# USB3HUB.net
KiCad netlist of a schematic drawn in Altium Designer
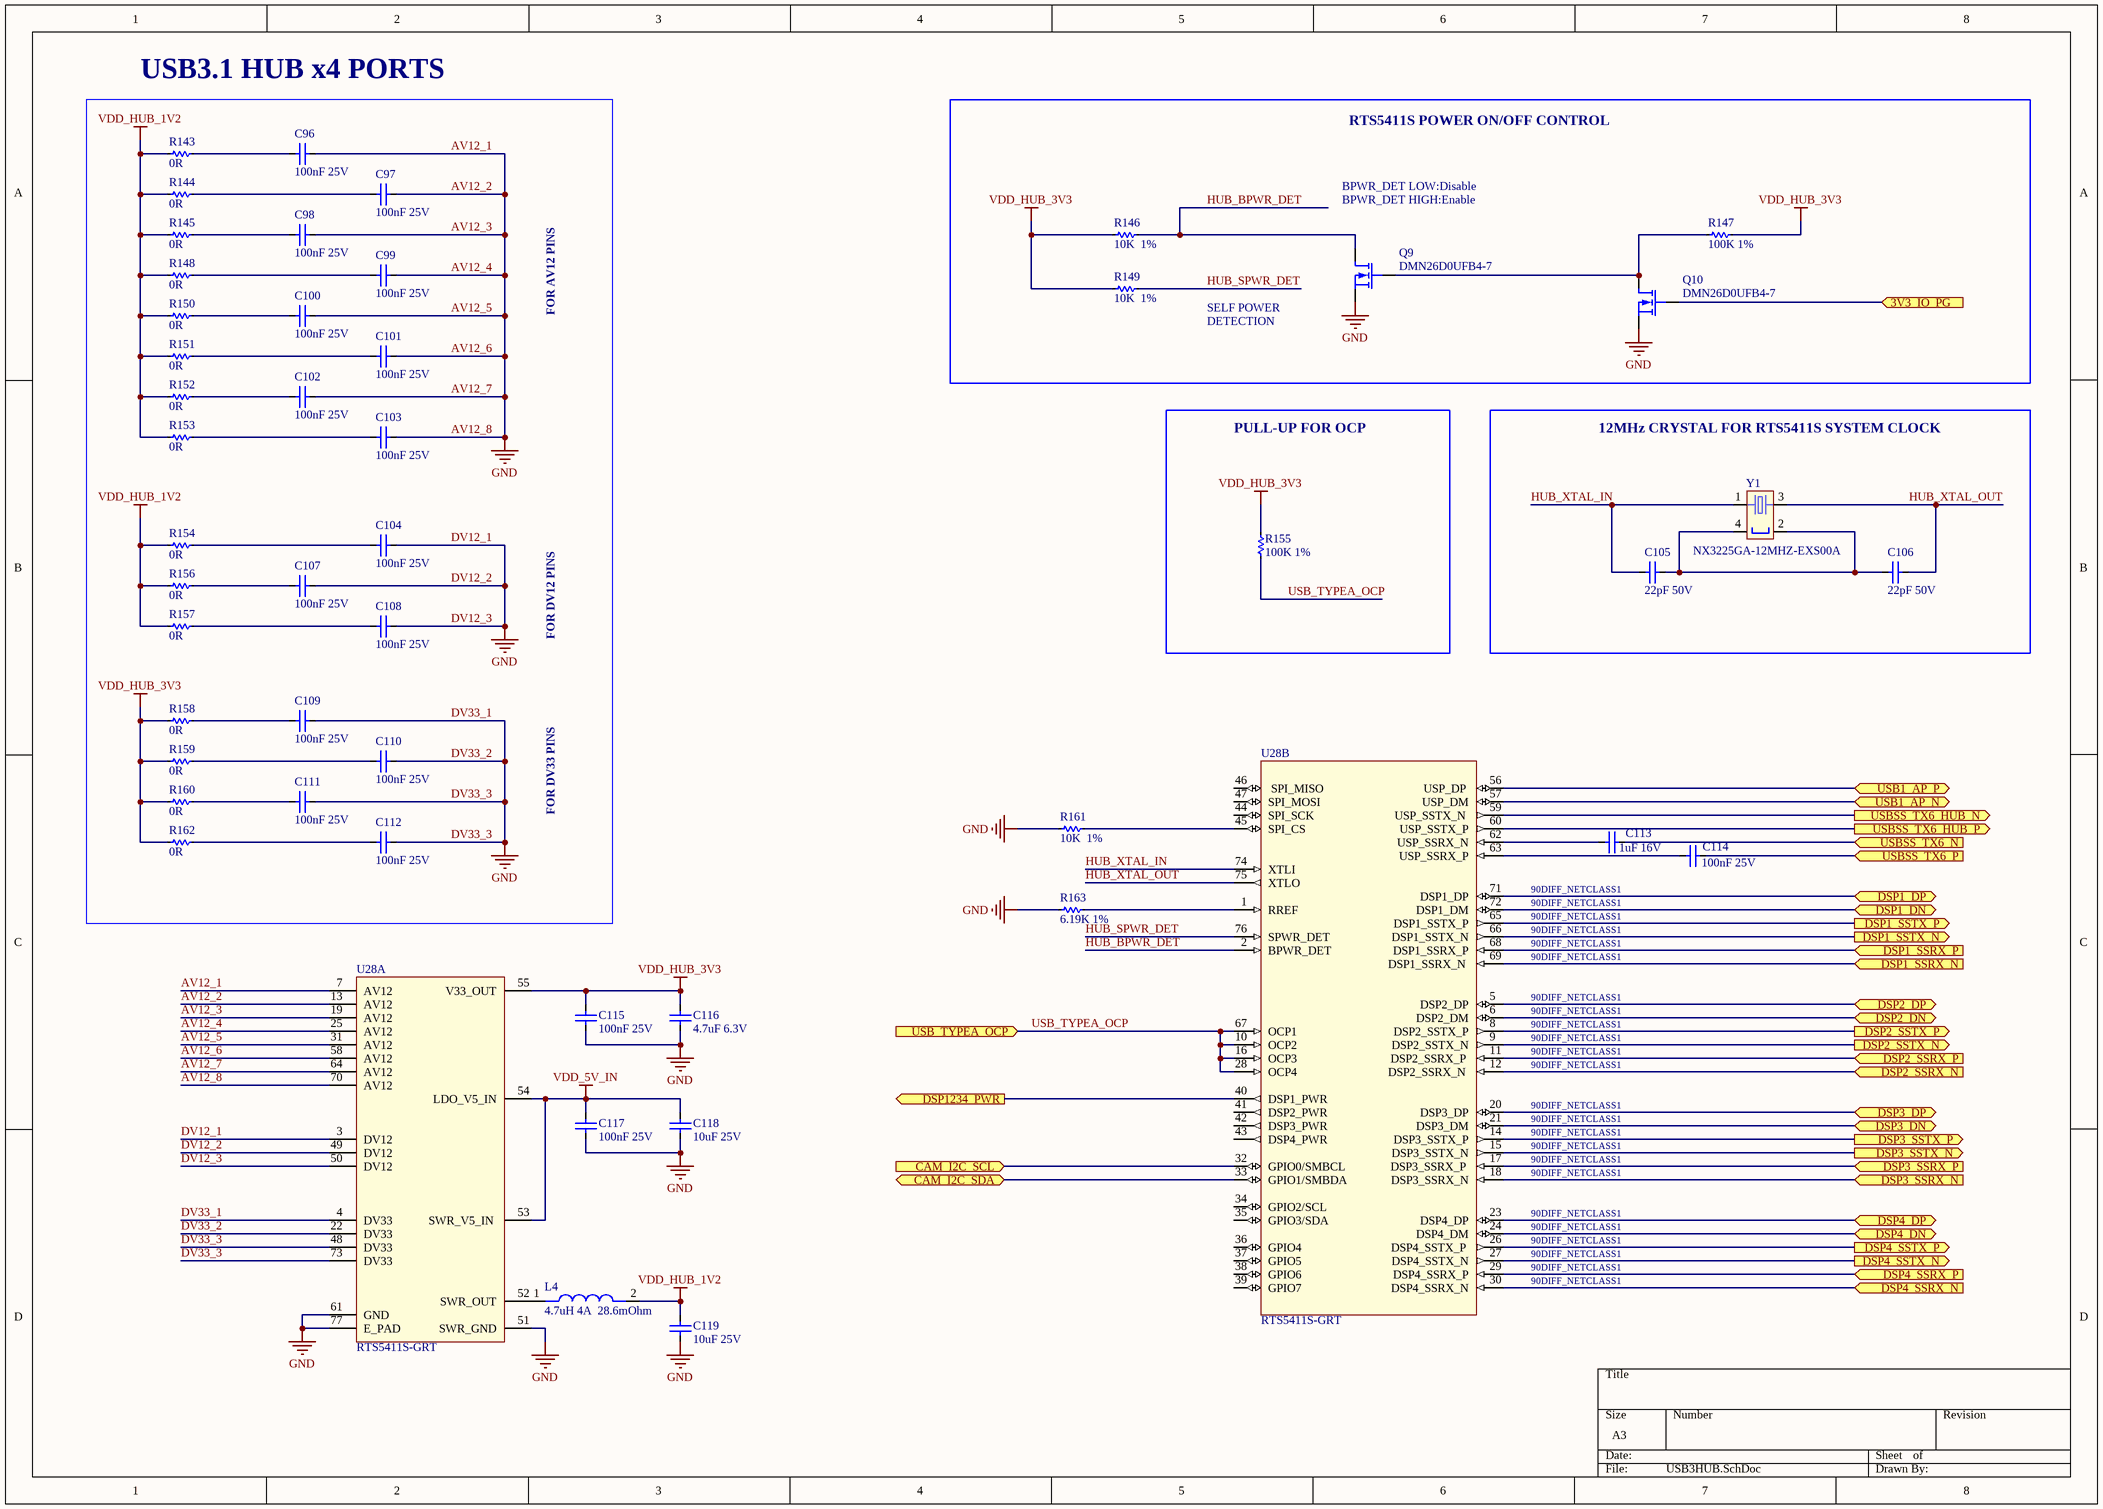
[diagram p0: USB3HUB.SchDoc]

(export (version "E")
  (design (tool "Eeschema 10.0.6"))
  (components
    (comp (ref "C96")
      (value "100nF 25V")
      (footprint "C0402")
      (description "CAP CER 0.1UF 25V X5R 0402 / High Value Multilayer Ceramic Capacitors (High dielectric type)")
      (fields
        (field (name "MANUFACTURER") "Taiyo Yuden")
        (field (name "MANUFACTURER PART NUMBER") "TMK105BJ104KV-F")
      )
      (libsource (lib "GM_Altium_Library") (part "TMK105BJ104KV-F"))
    )
    (comp (ref "C97")
      (value "100nF 25V")
      (footprint "C0402")
      (description "CAP CER 0.1UF 25V X5R 0402 / High Value Multilayer Ceramic Capacitors (High dielectric type)")
      (fields
        (field (name "MANUFACTURER") "Taiyo Yuden")
        (field (name "MANUFACTURER PART NUMBER") "TMK105BJ104KV-F")
      )
      (libsource (lib "GM_Altium_Library") (part "TMK105BJ104KV-F"))
    )
    (comp (ref "C98")
      (value "100nF 25V")
      (footprint "C0402")
      (description "CAP CER 0.1UF 25V X5R 0402 / High Value Multilayer Ceramic Capacitors (High dielectric type)")
      (fields
        (field (name "MANUFACTURER") "Taiyo Yuden")
        (field (name "MANUFACTURER PART NUMBER") "TMK105BJ104KV-F")
      )
      (libsource (lib "GM_Altium_Library") (part "TMK105BJ104KV-F"))
    )
    (comp (ref "C99")
      (value "100nF 25V")
      (footprint "C0402")
      (description "CAP CER 0.1UF 25V X5R 0402 / High Value Multilayer Ceramic Capacitors (High dielectric type)")
      (fields
        (field (name "MANUFACTURER") "Taiyo Yuden")
        (field (name "MANUFACTURER PART NUMBER") "TMK105BJ104KV-F")
      )
      (libsource (lib "GM_Altium_Library") (part "TMK105BJ104KV-F"))
    )
    (comp (ref "C100")
      (value "100nF 25V")
      (footprint "C0402")
      (description "CAP CER 0.1UF 25V X5R 0402 / High Value Multilayer Ceramic Capacitors (High dielectric type)")
      (fields
        (field (name "MANUFACTURER") "Taiyo Yuden")
        (field (name "MANUFACTURER PART NUMBER") "TMK105BJ104KV-F")
      )
      (libsource (lib "GM_Altium_Library") (part "TMK105BJ104KV-F"))
    )
    (comp (ref "C101")
      (value "100nF 25V")
      (footprint "C0402")
      (description "CAP CER 0.1UF 25V X5R 0402 / High Value Multilayer Ceramic Capacitors (High dielectric type)")
      (fields
        (field (name "MANUFACTURER") "Taiyo Yuden")
        (field (name "MANUFACTURER PART NUMBER") "TMK105BJ104KV-F")
      )
      (libsource (lib "GM_Altium_Library") (part "TMK105BJ104KV-F"))
    )
    (comp (ref "C102")
      (value "100nF 25V")
      (footprint "C0402")
      (description "CAP CER 0.1UF 25V X5R 0402 / High Value Multilayer Ceramic Capacitors (High dielectric type)")
      (fields
        (field (name "MANUFACTURER") "Taiyo Yuden")
        (field (name "MANUFACTURER PART NUMBER") "TMK105BJ104KV-F")
      )
      (libsource (lib "GM_Altium_Library") (part "TMK105BJ104KV-F"))
    )
    (comp (ref "C103")
      (value "100nF 25V")
      (footprint "C0402")
      (description "CAP CER 0.1UF 25V X5R 0402 / High Value Multilayer Ceramic Capacitors (High dielectric type)")
      (fields
        (field (name "MANUFACTURER") "Taiyo Yuden")
        (field (name "MANUFACTURER PART NUMBER") "TMK105BJ104KV-F")
      )
      (libsource (lib "GM_Altium_Library") (part "TMK105BJ104KV-F"))
    )
    (comp (ref "C104")
      (value "100nF 25V")
      (footprint "C0402")
      (description "CAP CER 0.1UF 25V X5R 0402 / High Value Multilayer Ceramic Capacitors (High dielectric type)")
      (fields
        (field (name "MANUFACTURER") "Taiyo Yuden")
        (field (name "MANUFACTURER PART NUMBER") "TMK105BJ104KV-F")
      )
      (libsource (lib "GM_Altium_Library") (part "TMK105BJ104KV-F"))
    )
    (comp (ref "C105")
      (value "22pF 50V")
      (footprint "C0402")
      (description "0402 22pF 50V ±5 % Tolerance C0G SMT Multilayer Ceramic Capacitor")
      (fields
        (field (name "MANUFACTURER") "Murata")
        (field (name "MANUFACTURER PART NUMBER") "GRM1555C1H220JA01D")
      )
      (libsource (lib "GM_Capacitor") (part "GRM1555C1H220JA01D"))
    )
    (comp (ref "C106")
      (value "22pF 50V")
      (footprint "C0402")
      (description "0402 22pF 50V ±5 % Tolerance C0G SMT Multilayer Ceramic Capacitor")
      (fields
        (field (name "MANUFACTURER") "Murata")
        (field (name "MANUFACTURER PART NUMBER") "GRM1555C1H220JA01D")
      )
      (libsource (lib "GM_Capacitor") (part "GRM1555C1H220JA01D"))
    )
    (comp (ref "C107")
      (value "100nF 25V")
      (footprint "C0402")
      (description "CAP CER 0.1UF 25V X5R 0402 / High Value Multilayer Ceramic Capacitors (High dielectric type)")
      (fields
        (field (name "MANUFACTURER") "Taiyo Yuden")
        (field (name "MANUFACTURER PART NUMBER") "TMK105BJ104KV-F")
      )
      (libsource (lib "GM_Altium_Library") (part "TMK105BJ104KV-F"))
    )
    (comp (ref "C108")
      (value "100nF 25V")
      (footprint "C0402")
      (description "CAP CER 0.1UF 25V X5R 0402 / High Value Multilayer Ceramic Capacitors (High dielectric type)")
      (fields
        (field (name "MANUFACTURER") "Taiyo Yuden")
        (field (name "MANUFACTURER PART NUMBER") "TMK105BJ104KV-F")
      )
      (libsource (lib "GM_Altium_Library") (part "TMK105BJ104KV-F"))
    )
    (comp (ref "C109")
      (value "100nF 25V")
      (footprint "C0402")
      (description "CAP CER 0.1UF 25V X5R 0402 / High Value Multilayer Ceramic Capacitors (High dielectric type)")
      (fields
        (field (name "MANUFACTURER") "Taiyo Yuden")
        (field (name "MANUFACTURER PART NUMBER") "TMK105BJ104KV-F")
      )
      (libsource (lib "GM_Altium_Library") (part "TMK105BJ104KV-F"))
    )
    (comp (ref "C110")
      (value "100nF 25V")
      (footprint "C0402")
      (description "CAP CER 0.1UF 25V X5R 0402 / High Value Multilayer Ceramic Capacitors (High dielectric type)")
      (fields
        (field (name "MANUFACTURER") "Taiyo Yuden")
        (field (name "MANUFACTURER PART NUMBER") "TMK105BJ104KV-F")
      )
      (libsource (lib "GM_Altium_Library") (part "TMK105BJ104KV-F"))
    )
    (comp (ref "C111")
      (value "100nF 25V")
      (footprint "C0402")
      (description "CAP CER 0.1UF 25V X5R 0402 / High Value Multilayer Ceramic Capacitors (High dielectric type)")
      (fields
        (field (name "MANUFACTURER") "Taiyo Yuden")
        (field (name "MANUFACTURER PART NUMBER") "TMK105BJ104KV-F")
      )
      (libsource (lib "GM_Altium_Library") (part "TMK105BJ104KV-F"))
    )
    (comp (ref "C112")
      (value "100nF 25V")
      (footprint "C0402")
      (description "CAP CER 0.1UF 25V X5R 0402 / High Value Multilayer Ceramic Capacitors (High dielectric type)")
      (fields
        (field (name "MANUFACTURER") "Taiyo Yuden")
        (field (name "MANUFACTURER PART NUMBER") "TMK105BJ104KV-F")
      )
      (libsource (lib "GM_Altium_Library") (part "TMK105BJ104KV-F"))
    )
    (comp (ref "C113")
      (value "1uF 16V")
      (footprint "C0603")
      (description "0603 1 uF 16 V ±10 % Tolerance X5R Surface Mount Multilayer Ceramic Capacitor")
      (fields
        (field (name "MANUFACTURER") "Kyocera AVX")
        (field (name "MANUFACTURER PART NUMBER") "0603YD105KAT2A")
      )
      (libsource (lib "GM_Altium_Library") (part "0603YD105KAT2A"))
    )
    (comp (ref "C114")
      (value "100nF 25V")
      (footprint "C0402")
      (description "CAP CER 0.1UF 25V X5R 0402 / High Value Multilayer Ceramic Capacitors (High dielectric type)")
      (fields
        (field (name "MANUFACTURER") "Taiyo Yuden")
        (field (name "MANUFACTURER PART NUMBER") "TMK105BJ104KV-F")
      )
      (libsource (lib "GM_Altium_Library") (part "TMK105BJ104KV-F"))
    )
    (comp (ref "C115")
      (value "100nF 25V")
      (footprint "C0402")
      (description "CAP CER 0.1UF 25V X5R 0402 / High Value Multilayer Ceramic Capacitors (High dielectric type)")
      (fields
        (field (name "MANUFACTURER") "Taiyo Yuden")
        (field (name "MANUFACTURER PART NUMBER") "TMK105BJ104KV-F")
      )
      (libsource (lib "GM_Altium_Library") (part "TMK105BJ104KV-F"))
    )
    (comp (ref "C116")
      (value "4.7uF 6.3V")
      (footprint "C0402")
      (description "CAP CER 4.7UF 6.3V X5R 0402")
      (fields
        (field (name "MANUFACTURER") "Samsung")
        (field (name "MANUFACTURER PART NUMBER") "CL05A475KQ5NRNC")
      )
      (libsource (lib "GM_Altium_Library") (part "CL05A475KQ5NRNC"))
    )
    (comp (ref "C117")
      (value "100nF 25V")
      (footprint "C0402")
      (description "CAP CER 0.1UF 25V X5R 0402 / High Value Multilayer Ceramic Capacitors (High dielectric type)")
      (fields
        (field (name "MANUFACTURER") "Taiyo Yuden")
        (field (name "MANUFACTURER PART NUMBER") "TMK105BJ104KV-F")
      )
      (libsource (lib "GM_Altium_Library") (part "TMK105BJ104KV-F"))
    )
    (comp (ref "C118")
      (value "10uF 25V")
      (footprint "C0805")
      (description "0805 10 uF 25 V ±10% Tolerance X5R SMT Multilayer Ceramic Capacitor")
      (fields
        (field (name "MANUFACTURER") "Taiyo Yuden")
        (field (name "MANUFACTURER PART NUMBER") "TMK212BBJ106KG-T")
      )
      (libsource (lib "GM_Altium_Library") (part "TMK212BBJ106KG-T"))
    )
    (comp (ref "C119")
      (value "10uF 25V")
      (footprint "C0805")
      (description "0805 10 uF 25 V ±10% Tolerance X5R SMT Multilayer Ceramic Capacitor")
      (fields
        (field (name "MANUFACTURER") "Taiyo Yuden")
        (field (name "MANUFACTURER PART NUMBER") "TMK212BBJ106KG-T")
      )
      (libsource (lib "GM_Altium_Library") (part "TMK212BBJ106KG-T"))
    )
    (comp (ref "L4")
      (value "4.7uH 4A  28.6mOhm")
      (footprint "NRS8030T4R7MJGJV")
      (description "Inductor Power Shielded Wirewound 4.7uH 20% 100KHz Ferrite 4A 0.0286Ohm DCR 3131 Automotive T/R")
      (fields
        (field (name "MANUFACTURER") "Taiyo Yuden")
        (field (name "MANUFACTURER PART NUMBER") "NRS8030T4R7MJGJV")
      )
      (libsource (lib "GM_Inductor") (part "NRS8030T4R7MJGJV"))
    )
    (comp (ref "Q9")
      (value "DMN26D0UFB4-7")
      (footprint "DFN1006-3")
      (description "Single N-Channel 20 V 350 mW Silicon Surface Mount Mosfet - DFN-3")
      (fields (field (name "MANUFACTURER") "Diodes"))
      (libsource (lib "GM_Altium_Library") (part "DMN26D0UFB4-7"))
    )
    (comp (ref "Q10")
      (value "DMN26D0UFB4-7")
      (footprint "DFN1006-3")
      (description "Single N-Channel 20 V 350 mW Silicon Surface Mount Mosfet - DFN-3")
      (fields (field (name "MANUFACTURER") "Diodes"))
      (libsource (lib "GM_Altium_Library") (part "DMN26D0UFB4-7"))
    )
    (comp (ref "R143")
      (value "0R")
      (footprint "R0603")
      (description "RES SMD 0 OHM JUMPER 1/10W 0603")
      (fields
        (field (name "MANUFACTURER") "Bourns")
        (field (name "MANUFACTURER PART NUMBER") "CR0603-J/-000ELF")
      )
      (libsource (lib "GM_Altium_Library") (part "CR0603-J/-000ELF"))
    )
    (comp (ref "R144")
      (value "0R")
      (footprint "R0603")
      (description "RES SMD 0 OHM JUMPER 1/10W 0603")
      (fields
        (field (name "MANUFACTURER") "Bourns")
        (field (name "MANUFACTURER PART NUMBER") "CR0603-J/-000ELF")
      )
      (libsource (lib "GM_Altium_Library") (part "CR0603-J/-000ELF"))
    )
    (comp (ref "R145")
      (value "0R")
      (footprint "R0603")
      (description "RES SMD 0 OHM JUMPER 1/10W 0603")
      (fields
        (field (name "MANUFACTURER") "Bourns")
        (field (name "MANUFACTURER PART NUMBER") "CR0603-J/-000ELF")
      )
      (libsource (lib "GM_Altium_Library") (part "CR0603-J/-000ELF"))
    )
    (comp (ref "R146")
      (value "10K  1%")
      (footprint "R0402")
      (description "Res General Purpose Thick Film 0402 10K Ohm 1% 1/16W ±100ppm/°C Molded SMD Paper T/R")
      (fields
        (field (name "MANUFACTURER") "Yageo")
        (field (name "MANUFACTURER PART NUMBER") "RC0402FR-0710KP")
      )
      (libsource (lib "GM_Altium_Library") (part "RC0402FR-0710KP"))
    )
    (comp (ref "R147")
      (value "100K 1%")
      (footprint "R0402")
      (description "RES SMD 100K OHM 1% 1/16W 0402")
      (fields
        (field (name "MANUFACTURER") "Yageo")
        (field (name "MANUFACTURER PART NUMBER") "RC0402FR-07100KL")
      )
      (libsource (lib "GM_Altium_Library") (part "RC0402FR-07100KL"))
    )
    (comp (ref "R148")
      (value "0R")
      (footprint "R0603")
      (description "RES SMD 0 OHM JUMPER 1/10W 0603")
      (fields
        (field (name "MANUFACTURER") "Bourns")
        (field (name "MANUFACTURER PART NUMBER") "CR0603-J/-000ELF")
      )
      (libsource (lib "GM_Altium_Library") (part "CR0603-J/-000ELF"))
    )
    (comp (ref "R149")
      (value "10K  1%")
      (footprint "R0402")
      (description "Res General Purpose Thick Film 0402 10K Ohm 1% 1/16W ±100ppm/°C Molded SMD Paper T/R")
      (fields
        (field (name "MANUFACTURER") "Yageo")
        (field (name "MANUFACTURER PART NUMBER") "RC0402FR-0710KP")
      )
      (libsource (lib "GM_Altium_Library") (part "RC0402FR-0710KP"))
    )
    (comp (ref "R150")
      (value "0R")
      (footprint "R0603")
      (description "RES SMD 0 OHM JUMPER 1/10W 0603")
      (fields
        (field (name "MANUFACTURER") "Bourns")
        (field (name "MANUFACTURER PART NUMBER") "CR0603-J/-000ELF")
      )
      (libsource (lib "GM_Altium_Library") (part "CR0603-J/-000ELF"))
    )
    (comp (ref "R151")
      (value "0R")
      (footprint "R0603")
      (description "RES SMD 0 OHM JUMPER 1/10W 0603")
      (fields
        (field (name "MANUFACTURER") "Bourns")
        (field (name "MANUFACTURER PART NUMBER") "CR0603-J/-000ELF")
      )
      (libsource (lib "GM_Altium_Library") (part "CR0603-J/-000ELF"))
    )
    (comp (ref "R152")
      (value "0R")
      (footprint "R0603")
      (description "RES SMD 0 OHM JUMPER 1/10W 0603")
      (fields
        (field (name "MANUFACTURER") "Bourns")
        (field (name "MANUFACTURER PART NUMBER") "CR0603-J/-000ELF")
      )
      (libsource (lib "GM_Altium_Library") (part "CR0603-J/-000ELF"))
    )
    (comp (ref "R153")
      (value "0R")
      (footprint "R0603")
      (description "RES SMD 0 OHM JUMPER 1/10W 0603")
      (fields
        (field (name "MANUFACTURER") "Bourns")
        (field (name "MANUFACTURER PART NUMBER") "CR0603-J/-000ELF")
      )
      (libsource (lib "GM_Altium_Library") (part "CR0603-J/-000ELF"))
    )
    (comp (ref "R154")
      (value "0R")
      (footprint "R0603")
      (description "RES SMD 0 OHM JUMPER 1/10W 0603")
      (fields
        (field (name "MANUFACTURER") "Bourns")
        (field (name "MANUFACTURER PART NUMBER") "CR0603-J/-000ELF")
      )
      (libsource (lib "GM_Altium_Library") (part "CR0603-J/-000ELF"))
    )
    (comp (ref "R155")
      (value "100K 1%")
      (footprint "R0402")
      (description "RES SMD 100K OHM 1% 1/16W 0402")
      (fields
        (field (name "MANUFACTURER") "Yageo")
        (field (name "MANUFACTURER PART NUMBER") "RC0402FR-07100KL")
      )
      (libsource (lib "GM_Altium_Library") (part "RC0402FR-07100KL"))
    )
    (comp (ref "R156")
      (value "0R")
      (footprint "R0603")
      (description "RES SMD 0 OHM JUMPER 1/10W 0603")
      (fields
        (field (name "MANUFACTURER") "Bourns")
        (field (name "MANUFACTURER PART NUMBER") "CR0603-J/-000ELF")
      )
      (libsource (lib "GM_Altium_Library") (part "CR0603-J/-000ELF"))
    )
    (comp (ref "R157")
      (value "0R")
      (footprint "R0603")
      (description "RES SMD 0 OHM JUMPER 1/10W 0603")
      (fields
        (field (name "MANUFACTURER") "Bourns")
        (field (name "MANUFACTURER PART NUMBER") "CR0603-J/-000ELF")
      )
      (libsource (lib "GM_Altium_Library") (part "CR0603-J/-000ELF"))
    )
    (comp (ref "R158")
      (value "0R")
      (footprint "R0603")
      (description "RES SMD 0 OHM JUMPER 1/10W 0603")
      (fields
        (field (name "MANUFACTURER") "Bourns")
        (field (name "MANUFACTURER PART NUMBER") "CR0603-J/-000ELF")
      )
      (libsource (lib "GM_Altium_Library") (part "CR0603-J/-000ELF"))
    )
    (comp (ref "R159")
      (value "0R")
      (footprint "R0603")
      (description "RES SMD 0 OHM JUMPER 1/10W 0603")
      (fields
        (field (name "MANUFACTURER") "Bourns")
        (field (name "MANUFACTURER PART NUMBER") "CR0603-J/-000ELF")
      )
      (libsource (lib "GM_Altium_Library") (part "CR0603-J/-000ELF"))
    )
    (comp (ref "R160")
      (value "0R")
      (footprint "R0603")
      (description "RES SMD 0 OHM JUMPER 1/10W 0603")
      (fields
        (field (name "MANUFACTURER") "Bourns")
        (field (name "MANUFACTURER PART NUMBER") "CR0603-J/-000ELF")
      )
      (libsource (lib "GM_Altium_Library") (part "CR0603-J/-000ELF"))
    )
    (comp (ref "R161")
      (value "10K  1%")
      (footprint "R0402")
      (description "Res General Purpose Thick Film 0402 10K Ohm 1% 1/16W ±100ppm/°C Molded SMD Paper T/R")
      (fields
        (field (name "MANUFACTURER") "Yageo")
        (field (name "MANUFACTURER PART NUMBER") "RC0402FR-0710KP")
      )
      (libsource (lib "GM_Altium_Library") (part "RC0402FR-0710KP"))
    )
    (comp (ref "R162")
      (value "0R")
      (footprint "R0603")
      (description "RES SMD 0 OHM JUMPER 1/10W 0603")
      (fields
        (field (name "MANUFACTURER") "Bourns")
        (field (name "MANUFACTURER PART NUMBER") "CR0603-J/-000ELF")
      )
      (libsource (lib "GM_Altium_Library") (part "CR0603-J/-000ELF"))
    )
    (comp (ref "R163")
      (value "6.19K 1%")
      (footprint "R0402")
      (description "Res Thick Film 0402 6.19K Ohm 1% 1/16W ±100ppm/°C Molded SMD Paper T/R")
      (fields
        (field (name "MANUFACTURER") "Yageo")
        (field (name "MANUFACTURER PART NUMBER") "RC0402FR-076K19L")
      )
      (libsource (lib "GM_Altium_Library") (part "RC0402FR-076K19L"))
    )
    (comp (ref "U28")
      (value "RTS5411S-GRT")
      (footprint "QFN-76")
      (description "USB 3.0 Super-Speed HUB Controller, 76-pin QFN (9 x9 mm) package")
      (libsource (lib "GM_Altium_Library") (part "RTS5411S-GRT"))
    )
    (comp (ref "Y1")
      (value "NX3225GA-12MHZ-EXS00A")
      (footprint "NX3225GA-12MHZ-EXS00A-CG07042")
      (description "Crystal 12.0000MHZ 10PF SMD")
      (fields
        (field (name "MANUFACTURER") "NDK")
        (field (name "MANUFACTURER PART NUMBER") "NX3225GA-12MHZ-EXS00A-CG07042")
      )
      (libsource (lib "GM_Crystal_Oscilator_Resonator") (part "NX3225GA-12MHZ-EXS00A-CG07042"))
    )
  )
  (nets
    (net (code "1") (name "/3V3_IO_PG") (class "Default")
      (node (ref "Q10") (pin "1") (pinfunction "G_1") (pintype "passive"))
    )
    (net (code "2") (name "/CAM_I2C_SCL") (class "Default")
      (node (ref "U28") (pin "32") (pinfunction "GPIO0/SMBCL_32") (pintype "bidirectional"))
    )
    (net (code "3") (name "/CAM_I2C_SDA") (class "Default")
      (node (ref "U28") (pin "33") (pinfunction "GPIO1/SMBDA_33") (pintype "bidirectional"))
    )
    (net (code "4") (name "/DSP1_DN") (class "Default")
      (node (ref "U28") (pin "72") (pinfunction "DSP1_DM_72") (pintype "bidirectional"))
    )
    (net (code "5") (name "/DSP1_DP") (class "Default")
      (node (ref "U28") (pin "71") (pinfunction "DSP1_DP_71") (pintype "bidirectional"))
    )
    (net (code "6") (name "/DSP1_SSRX_N") (class "Default")
      (node (ref "U28") (pin "69") (pinfunction "DSP1_SSRX_N_69") (pintype "input"))
    )
    (net (code "7") (name "/DSP1_SSRX_P") (class "Default")
      (node (ref "U28") (pin "68") (pinfunction "DSP1_SSRX_P_68") (pintype "input"))
    )
    (net (code "8") (name "/DSP1_SSTX_N") (class "Default")
      (node (ref "U28") (pin "66") (pinfunction "DSP1_SSTX_N_66") (pintype "output"))
    )
    (net (code "9") (name "/DSP1_SSTX_P") (class "Default")
      (node (ref "U28") (pin "65") (pinfunction "DSP1_SSTX_P_65") (pintype "output"))
    )
    (net (code "10") (name "/DSP2_DN") (class "Default")
      (node (ref "U28") (pin "6") (pinfunction "DSP2_DM_6") (pintype "bidirectional"))
    )
    (net (code "11") (name "/DSP2_DP") (class "Default")
      (node (ref "U28") (pin "5") (pinfunction "DSP2_DP_5") (pintype "bidirectional"))
    )
    (net (code "12") (name "/DSP2_SSRX_N") (class "Default")
      (node (ref "U28") (pin "12") (pinfunction "DSP2_SSRX_N_12") (pintype "input"))
    )
    (net (code "13") (name "/DSP2_SSRX_P") (class "Default")
      (node (ref "U28") (pin "11") (pinfunction "DSP2_SSRX_P_11") (pintype "input"))
    )
    (net (code "14") (name "/DSP2_SSTX_N") (class "Default")
      (node (ref "U28") (pin "9") (pinfunction "DSP2_SSTX_N_9") (pintype "output"))
    )
    (net (code "15") (name "/DSP2_SSTX_P") (class "Default")
      (node (ref "U28") (pin "8") (pinfunction "DSP2_SSTX_P_8") (pintype "output"))
    )
    (net (code "16") (name "/DSP3_DN") (class "Default")
      (node (ref "U28") (pin "21") (pinfunction "DSP3_DM_21") (pintype "bidirectional"))
    )
    (net (code "17") (name "/DSP3_DP") (class "Default")
      (node (ref "U28") (pin "20") (pinfunction "DSP3_DP_20") (pintype "bidirectional"))
    )
    (net (code "18") (name "/DSP3_SSRX_N") (class "Default")
      (node (ref "U28") (pin "18") (pinfunction "DSP3_SSRX_N_18") (pintype "input"))
    )
    (net (code "19") (name "/DSP3_SSRX_P") (class "Default")
      (node (ref "U28") (pin "17") (pinfunction "DSP3_SSRX_P_17") (pintype "input"))
    )
    (net (code "20") (name "/DSP3_SSTX_N") (class "Default")
      (node (ref "U28") (pin "15") (pinfunction "DSP3_SSTX_N_15") (pintype "output"))
    )
    (net (code "21") (name "/DSP3_SSTX_P") (class "Default")
      (node (ref "U28") (pin "14") (pinfunction "DSP3_SSTX_P_14") (pintype "output"))
    )
    (net (code "22") (name "/DSP4_DN") (class "Default")
      (node (ref "U28") (pin "24") (pinfunction "DSP4_DM_24") (pintype "bidirectional"))
    )
    (net (code "23") (name "/DSP4_DP") (class "Default")
      (node (ref "U28") (pin "23") (pinfunction "DSP4_DP_23") (pintype "bidirectional"))
    )
    (net (code "24") (name "/DSP4_SSRX_N") (class "Default")
      (node (ref "U28") (pin "30") (pinfunction "DSP4_SSRX_N_30") (pintype "input"))
    )
    (net (code "25") (name "/DSP4_SSRX_P") (class "Default")
      (node (ref "U28") (pin "29") (pinfunction "DSP4_SSRX_P_29") (pintype "input"))
    )
    (net (code "26") (name "/DSP4_SSTX_N") (class "Default")
      (node (ref "U28") (pin "27") (pinfunction "DSP4_SSTX_N_27") (pintype "output"))
    )
    (net (code "27") (name "/DSP4_SSTX_P") (class "Default")
      (node (ref "U28") (pin "26") (pinfunction "DSP4_SSTX_P_26") (pintype "output"))
    )
    (net (code "28") (name "/DSP1234_PWR") (class "Default")
      (node (ref "U28") (pin "40") (pinfunction "DSP1_PWR_40") (pintype "output"))
    )
    (net (code "29") (name "/HUB_BPWR_DET") (class "Default")
      (node (ref "Q9") (pin "3") (pinfunction "D_3") (pintype "passive"))
      (node (ref "R146") (pin "2") (pinfunction "2_2") (pintype "passive"))
      (node (ref "U28") (pin "2") (pinfunction "BPWR_DET_2") (pintype "input"))
    )
    (net (code "30") (name "/HUB_SPWR_DET") (class "Default")
      (node (ref "R149") (pin "2") (pinfunction "2_2") (pintype "passive"))
      (node (ref "U28") (pin "76") (pinfunction "SPWR_DET_76") (pintype "input"))
    )
    (net (code "31") (name "/HUB_XTAL_IN") (class "Default")
      (node (ref "C105") (pin "1") (pinfunction "1_1") (pintype "passive"))
      (node (ref "U28") (pin "74") (pinfunction "XTLI_74") (pintype "input"))
      (node (ref "Y1") (pin "1") (pinfunction "1_1") (pintype "passive"))
    )
    (net (code "32") (name "/HUB_XTAL_OUT") (class "Default")
      (node (ref "C106") (pin "1") (pinfunction "1_1") (pintype "passive"))
      (node (ref "U28") (pin "75") (pinfunction "XTLO_75") (pintype "output"))
      (node (ref "Y1") (pin "3") (pinfunction "3_3") (pintype "passive"))
    )
    (net (code "33") (name "/USB1_AP_N") (class "Default")
      (node (ref "U28") (pin "57") (pinfunction "USP_DM_57") (pintype "bidirectional"))
    )
    (net (code "34") (name "/USB1_AP_P") (class "Default")
      (node (ref "U28") (pin "56") (pinfunction "USP_DP_56") (pintype "bidirectional"))
    )
    (net (code "35") (name "/USBSS_TX6_HUB_N") (class "Default")
      (node (ref "U28") (pin "59") (pinfunction "USP_SSTX_N_59") (pintype "output"))
    )
    (net (code "36") (name "/USBSS_TX6_HUB_P") (class "Default")
      (node (ref "U28") (pin "60") (pinfunction "USP_SSTX_P_60") (pintype "output"))
    )
    (net (code "37") (name "/USBSS_TX6_N") (class "Default")
      (node (ref "C113") (pin "2") (pinfunction "2_2") (pintype "passive"))
    )
    (net (code "38") (name "/USBSS_TX6_P") (class "Default")
      (node (ref "C114") (pin "2") (pinfunction "2_2") (pintype "passive"))
    )
    (net (code "39") (name "/USB_TYPEA_OCP") (class "Default")
      (node (ref "R155") (pin "1") (pinfunction "1_1") (pintype "passive"))
      (node (ref "U28") (pin "10") (pinfunction "OCP2_10") (pintype "input"))
      (node (ref "U28") (pin "16") (pinfunction "OCP3_16") (pintype "input"))
      (node (ref "U28") (pin "28") (pinfunction "OCP4_28") (pintype "input"))
      (node (ref "U28") (pin "67") (pinfunction "OCP1_67") (pintype "input"))
    )
    (net (code "40") (name "GND") (class "Default")
      (node (ref "C100") (pin "2") (pinfunction "2_2") (pintype "passive"))
      (node (ref "C101") (pin "2") (pinfunction "2_2") (pintype "passive"))
      (node (ref "C102") (pin "2") (pinfunction "2_2") (pintype "passive"))
      (node (ref "C103") (pin "2") (pinfunction "2_2") (pintype "passive"))
      (node (ref "C104") (pin "2") (pinfunction "2_2") (pintype "passive"))
      (node (ref "C107") (pin "2") (pinfunction "2_2") (pintype "passive"))
      (node (ref "C108") (pin "2") (pinfunction "2_2") (pintype "passive"))
      (node (ref "C109") (pin "2") (pinfunction "2_2") (pintype "passive"))
      (node (ref "C110") (pin "2") (pinfunction "2_2") (pintype "passive"))
      (node (ref "C111") (pin "2") (pinfunction "2_2") (pintype "passive"))
      (node (ref "C112") (pin "2") (pinfunction "2_2") (pintype "passive"))
      (node (ref "C115") (pin "1") (pinfunction "1_1") (pintype "passive"))
      (node (ref "C116") (pin "1") (pinfunction "1_1") (pintype "passive"))
      (node (ref "C117") (pin "1") (pinfunction "1_1") (pintype "passive"))
      (node (ref "C118") (pin "1") (pinfunction "1_1") (pintype "passive"))
      (node (ref "C119") (pin "1") (pinfunction "1_1") (pintype "passive"))
      (node (ref "C96") (pin "2") (pinfunction "2_2") (pintype "passive"))
      (node (ref "C97") (pin "2") (pinfunction "2_2") (pintype "passive"))
      (node (ref "C98") (pin "2") (pinfunction "2_2") (pintype "passive"))
      (node (ref "C99") (pin "2") (pinfunction "2_2") (pintype "passive"))
      (node (ref "Q10") (pin "2") (pinfunction "S_2") (pintype "passive"))
      (node (ref "Q9") (pin "2") (pinfunction "S_2") (pintype "passive"))
      (node (ref "R161") (pin "1") (pinfunction "1_1") (pintype "passive"))
      (node (ref "R163") (pin "1") (pinfunction "1_1") (pintype "passive"))
      (node (ref "U28") (pin "13") (pinfunction "AV12_13") (pintype "power_in"))
      (node (ref "U28") (pin "19") (pinfunction "AV12_19") (pintype "power_in"))
      (node (ref "U28") (pin "22") (pinfunction "DV33_22") (pintype "power_in"))
      (node (ref "U28") (pin "25") (pinfunction "AV12_25") (pintype "power_in"))
      (node (ref "U28") (pin "3") (pinfunction "DV12_3") (pintype "power_in"))
      (node (ref "U28") (pin "31") (pinfunction "AV12_31") (pintype "power_in"))
      (node (ref "U28") (pin "4") (pinfunction "DV33_4") (pintype "power_in"))
      (node (ref "U28") (pin "48") (pinfunction "DV33_48") (pintype "power_in"))
      (node (ref "U28") (pin "49") (pinfunction "DV12_49") (pintype "power_in"))
      (node (ref "U28") (pin "50") (pinfunction "DV12_50") (pintype "power_in"))
      (node (ref "U28") (pin "51") (pinfunction "SWR_GND_51") (pintype "power_in"))
      (node (ref "U28") (pin "58") (pinfunction "AV12_58") (pintype "power_in"))
      (node (ref "U28") (pin "61") (pinfunction "GND_61") (pintype "power_in"))
      (node (ref "U28") (pin "64") (pinfunction "AV12_64") (pintype "power_in"))
      (node (ref "U28") (pin "7") (pinfunction "AV12_7") (pintype "power_in"))
      (node (ref "U28") (pin "70") (pinfunction "AV12_70") (pintype "power_in"))
      (node (ref "U28") (pin "73") (pinfunction "DV33_73") (pintype "power_in"))
      (node (ref "U28") (pin "77") (pinfunction "E_PAD_77") (pintype "power_in"))
    )
    (net (code "41") (name "Net-(C96-Pad1)") (class "Default")
      (node (ref "C96") (pin "1") (pinfunction "1_1") (pintype "passive"))
      (node (ref "R143") (pin "2") (pinfunction "2_2") (pintype "passive"))
    )
    (net (code "42") (name "Net-(C97-Pad1)") (class "Default")
      (node (ref "C97") (pin "1") (pinfunction "1_1") (pintype "passive"))
      (node (ref "R144") (pin "2") (pinfunction "2_2") (pintype "passive"))
    )
    (net (code "43") (name "Net-(C98-Pad1)") (class "Default")
      (node (ref "C98") (pin "1") (pinfunction "1_1") (pintype "passive"))
      (node (ref "R145") (pin "2") (pinfunction "2_2") (pintype "passive"))
    )
    (net (code "44") (name "Net-(C99-Pad1)") (class "Default")
      (node (ref "C99") (pin "1") (pinfunction "1_1") (pintype "passive"))
      (node (ref "R148") (pin "2") (pinfunction "2_2") (pintype "passive"))
    )
    (net (code "45") (name "Net-(C100-Pad1)") (class "Default")
      (node (ref "C100") (pin "1") (pinfunction "1_1") (pintype "passive"))
      (node (ref "R150") (pin "2") (pinfunction "2_2") (pintype "passive"))
    )
    (net (code "46") (name "Net-(C101-Pad1)") (class "Default")
      (node (ref "C101") (pin "1") (pinfunction "1_1") (pintype "passive"))
      (node (ref "R151") (pin "2") (pinfunction "2_2") (pintype "passive"))
    )
    (net (code "47") (name "Net-(C102-Pad1)") (class "Default")
      (node (ref "C102") (pin "1") (pinfunction "1_1") (pintype "passive"))
      (node (ref "R152") (pin "2") (pinfunction "2_2") (pintype "passive"))
    )
    (net (code "48") (name "Net-(C103-Pad1)") (class "Default")
      (node (ref "C103") (pin "1") (pinfunction "1_1") (pintype "passive"))
      (node (ref "R153") (pin "2") (pinfunction "2_2") (pintype "passive"))
    )
    (net (code "49") (name "Net-(C104-Pad1)") (class "Default")
      (node (ref "C104") (pin "1") (pinfunction "1_1") (pintype "passive"))
      (node (ref "R154") (pin "2") (pinfunction "2_2") (pintype "passive"))
    )
    (net (code "50") (name "Net-(C105-Pad2)") (class "Default")
      (node (ref "C105") (pin "2") (pinfunction "2_2") (pintype "passive"))
      (node (ref "C106") (pin "2") (pinfunction "2_2") (pintype "passive"))
      (node (ref "Y1") (pin "2") (pinfunction "GND_2") (pintype "power_in"))
      (node (ref "Y1") (pin "4") (pinfunction "GND_4") (pintype "power_in"))
    )
    (net (code "51") (name "Net-(C107-Pad1)") (class "Default")
      (node (ref "C107") (pin "1") (pinfunction "1_1") (pintype "passive"))
      (node (ref "R156") (pin "2") (pinfunction "2_2") (pintype "passive"))
    )
    (net (code "52") (name "Net-(C108-Pad1)") (class "Default")
      (node (ref "C108") (pin "1") (pinfunction "1_1") (pintype "passive"))
      (node (ref "R157") (pin "2") (pinfunction "2_2") (pintype "passive"))
    )
    (net (code "53") (name "Net-(C109-Pad1)") (class "Default")
      (node (ref "C109") (pin "1") (pinfunction "1_1") (pintype "passive"))
      (node (ref "R158") (pin "2") (pinfunction "2_2") (pintype "passive"))
    )
    (net (code "54") (name "Net-(C110-Pad1)") (class "Default")
      (node (ref "C110") (pin "1") (pinfunction "1_1") (pintype "passive"))
      (node (ref "R159") (pin "2") (pinfunction "2_2") (pintype "passive"))
    )
    (net (code "55") (name "Net-(C111-Pad1)") (class "Default")
      (node (ref "C111") (pin "1") (pinfunction "1_1") (pintype "passive"))
      (node (ref "R160") (pin "2") (pinfunction "2_2") (pintype "passive"))
    )
    (net (code "56") (name "Net-(C112-Pad1)") (class "Default")
      (node (ref "C112") (pin "1") (pinfunction "1_1") (pintype "passive"))
      (node (ref "R162") (pin "2") (pinfunction "2_2") (pintype "passive"))
    )
    (net (code "57") (name "Net-(Q10-D)") (class "Default")
      (node (ref "Q10") (pin "3") (pinfunction "D_3") (pintype "passive"))
      (node (ref "Q9") (pin "1") (pinfunction "G_1") (pintype "passive"))
      (node (ref "R147") (pin "1") (pinfunction "1_1") (pintype "passive"))
    )
    (net (code "58") (name "Net-(U28A-SWR_OUT)") (class "Default")
      (node (ref "L4") (pin "1") (pinfunction "1_1") (pintype "passive"))
      (node (ref "U28") (pin "52") (pinfunction "SWR_OUT_52") (pintype "power_in"))
    )
    (net (code "59") (name "Net-(U28B-RREF)") (class "Default")
      (node (ref "R163") (pin "2") (pinfunction "2_2") (pintype "passive"))
      (node (ref "U28") (pin "1") (pinfunction "RREF_1") (pintype "input"))
    )
    (net (code "60") (name "Net-(U28B-SPI_CS)") (class "Default")
      (node (ref "R161") (pin "2") (pinfunction "2_2") (pintype "passive"))
      (node (ref "U28") (pin "45") (pinfunction "SPI_CS_45") (pintype "bidirectional"))
    )
    (net (code "61") (name "Net-(U28B-USP_SSRX_N)") (class "Default")
      (node (ref "C113") (pin "1") (pinfunction "1_1") (pintype "passive"))
      (node (ref "U28") (pin "62") (pinfunction "USP_SSRX_N_62") (pintype "input"))
    )
    (net (code "62") (name "Net-(U28B-USP_SSRX_P)") (class "Default")
      (node (ref "C114") (pin "1") (pinfunction "1_1") (pintype "passive"))
      (node (ref "U28") (pin "63") (pinfunction "USP_SSRX_P_63") (pintype "input"))
    )
    (net (code "63") (name "VDD_5V_IN") (class "Default")
      (node (ref "C117") (pin "2") (pinfunction "2_2") (pintype "passive"))
      (node (ref "C118") (pin "2") (pinfunction "2_2") (pintype "passive"))
      (node (ref "U28") (pin "53") (pinfunction "SWR_V5_IN_53") (pintype "power_in"))
      (node (ref "U28") (pin "54") (pinfunction "LDO_V5_IN_54") (pintype "power_in"))
    )
    (net (code "64") (name "VDD_HUB_1V2") (class "Default")
      (node (ref "C119") (pin "2") (pinfunction "2_2") (pintype "passive"))
      (node (ref "L4") (pin "2") (pinfunction "2_2") (pintype "passive"))
      (node (ref "R143") (pin "1") (pinfunction "1_1") (pintype "passive"))
      (node (ref "R144") (pin "1") (pinfunction "1_1") (pintype "passive"))
      (node (ref "R145") (pin "1") (pinfunction "1_1") (pintype "passive"))
      (node (ref "R148") (pin "1") (pinfunction "1_1") (pintype "passive"))
      (node (ref "R150") (pin "1") (pinfunction "1_1") (pintype "passive"))
      (node (ref "R151") (pin "1") (pinfunction "1_1") (pintype "passive"))
      (node (ref "R152") (pin "1") (pinfunction "1_1") (pintype "passive"))
      (node (ref "R153") (pin "1") (pinfunction "1_1") (pintype "passive"))
      (node (ref "R154") (pin "1") (pinfunction "1_1") (pintype "passive"))
      (node (ref "R156") (pin "1") (pinfunction "1_1") (pintype "passive"))
      (node (ref "R157") (pin "1") (pinfunction "1_1") (pintype "passive"))
    )
    (net (code "65") (name "VDD_HUB_3V3") (class "Default")
      (node (ref "C115") (pin "2") (pinfunction "2_2") (pintype "passive"))
      (node (ref "C116") (pin "2") (pinfunction "2_2") (pintype "passive"))
      (node (ref "R146") (pin "1") (pinfunction "1_1") (pintype "passive"))
      (node (ref "R147") (pin "2") (pinfunction "2_2") (pintype "passive"))
      (node (ref "R149") (pin "1") (pinfunction "1_1") (pintype "passive"))
      (node (ref "R155") (pin "2") (pinfunction "2_2") (pintype "passive"))
      (node (ref "R158") (pin "1") (pinfunction "1_1") (pintype "passive"))
      (node (ref "R159") (pin "1") (pinfunction "1_1") (pintype "passive"))
      (node (ref "R160") (pin "1") (pinfunction "1_1") (pintype "passive"))
      (node (ref "R162") (pin "1") (pinfunction "1_1") (pintype "passive"))
      (node (ref "U28") (pin "55") (pinfunction "V33_OUT_55") (pintype "power_in"))
    )
    (net (code "66") (name "unconnected-(U28B-DSP2_PWR-Pad41)") (class "Default")
      (node (ref "U28") (pin "41") (pinfunction "DSP2_PWR_41") (pintype "output"))
    )
    (net (code "67") (name "unconnected-(U28B-DSP3_PWR-Pad42)") (class "Default")
      (node (ref "U28") (pin "42") (pinfunction "DSP3_PWR_42") (pintype "output"))
    )
    (net (code "68") (name "unconnected-(U28B-DSP4_PWR-Pad43)") (class "Default")
      (node (ref "U28") (pin "43") (pinfunction "DSP4_PWR_43") (pintype "output"))
    )
    (net (code "69") (name "unconnected-(U28B-GPIO2{slash}SCL-Pad34)") (class "Default")
      (node (ref "U28") (pin "34") (pinfunction "GPIO2/SCL_34") (pintype "bidirectional"))
    )
    (net (code "70") (name "unconnected-(U28B-GPIO3{slash}SDA-Pad35)") (class "Default")
      (node (ref "U28") (pin "35") (pinfunction "GPIO3/SDA_35") (pintype "bidirectional"))
    )
    (net (code "71") (name "unconnected-(U28B-GPIO4-Pad36)") (class "Default")
      (node (ref "U28") (pin "36") (pinfunction "GPIO4_36") (pintype "bidirectional"))
    )
    (net (code "72") (name "unconnected-(U28B-GPIO5-Pad37)") (class "Default")
      (node (ref "U28") (pin "37") (pinfunction "GPIO5_37") (pintype "bidirectional"))
    )
    (net (code "73") (name "unconnected-(U28B-GPIO6-Pad38)") (class "Default")
      (node (ref "U28") (pin "38") (pinfunction "GPIO6_38") (pintype "bidirectional"))
    )
    (net (code "74") (name "unconnected-(U28B-GPIO7-Pad39)") (class "Default")
      (node (ref "U28") (pin "39") (pinfunction "GPIO7_39") (pintype "bidirectional"))
    )
    (net (code "75") (name "unconnected-(U28B-SPI_MOSI-Pad47)") (class "Default")
      (node (ref "U28") (pin "47") (pinfunction "SPI_MOSI_47") (pintype "bidirectional"))
    )
    (net (code "76") (name "unconnected-(U28B-SPI_SCK-Pad44)") (class "Default")
      (node (ref "U28") (pin "44") (pinfunction "SPI_SCK_44") (pintype "bidirectional"))
    )
    (net (code "77") (name "unconnected-(U28B-_SPI_MISO-Pad46)") (class "Default")
      (node (ref "U28") (pin "46") (pinfunction "_SPI_MISO_46") (pintype "bidirectional"))
    )
  )
)
